# RF.net
KiCad netlist of a schematic drawn in Altium Designer
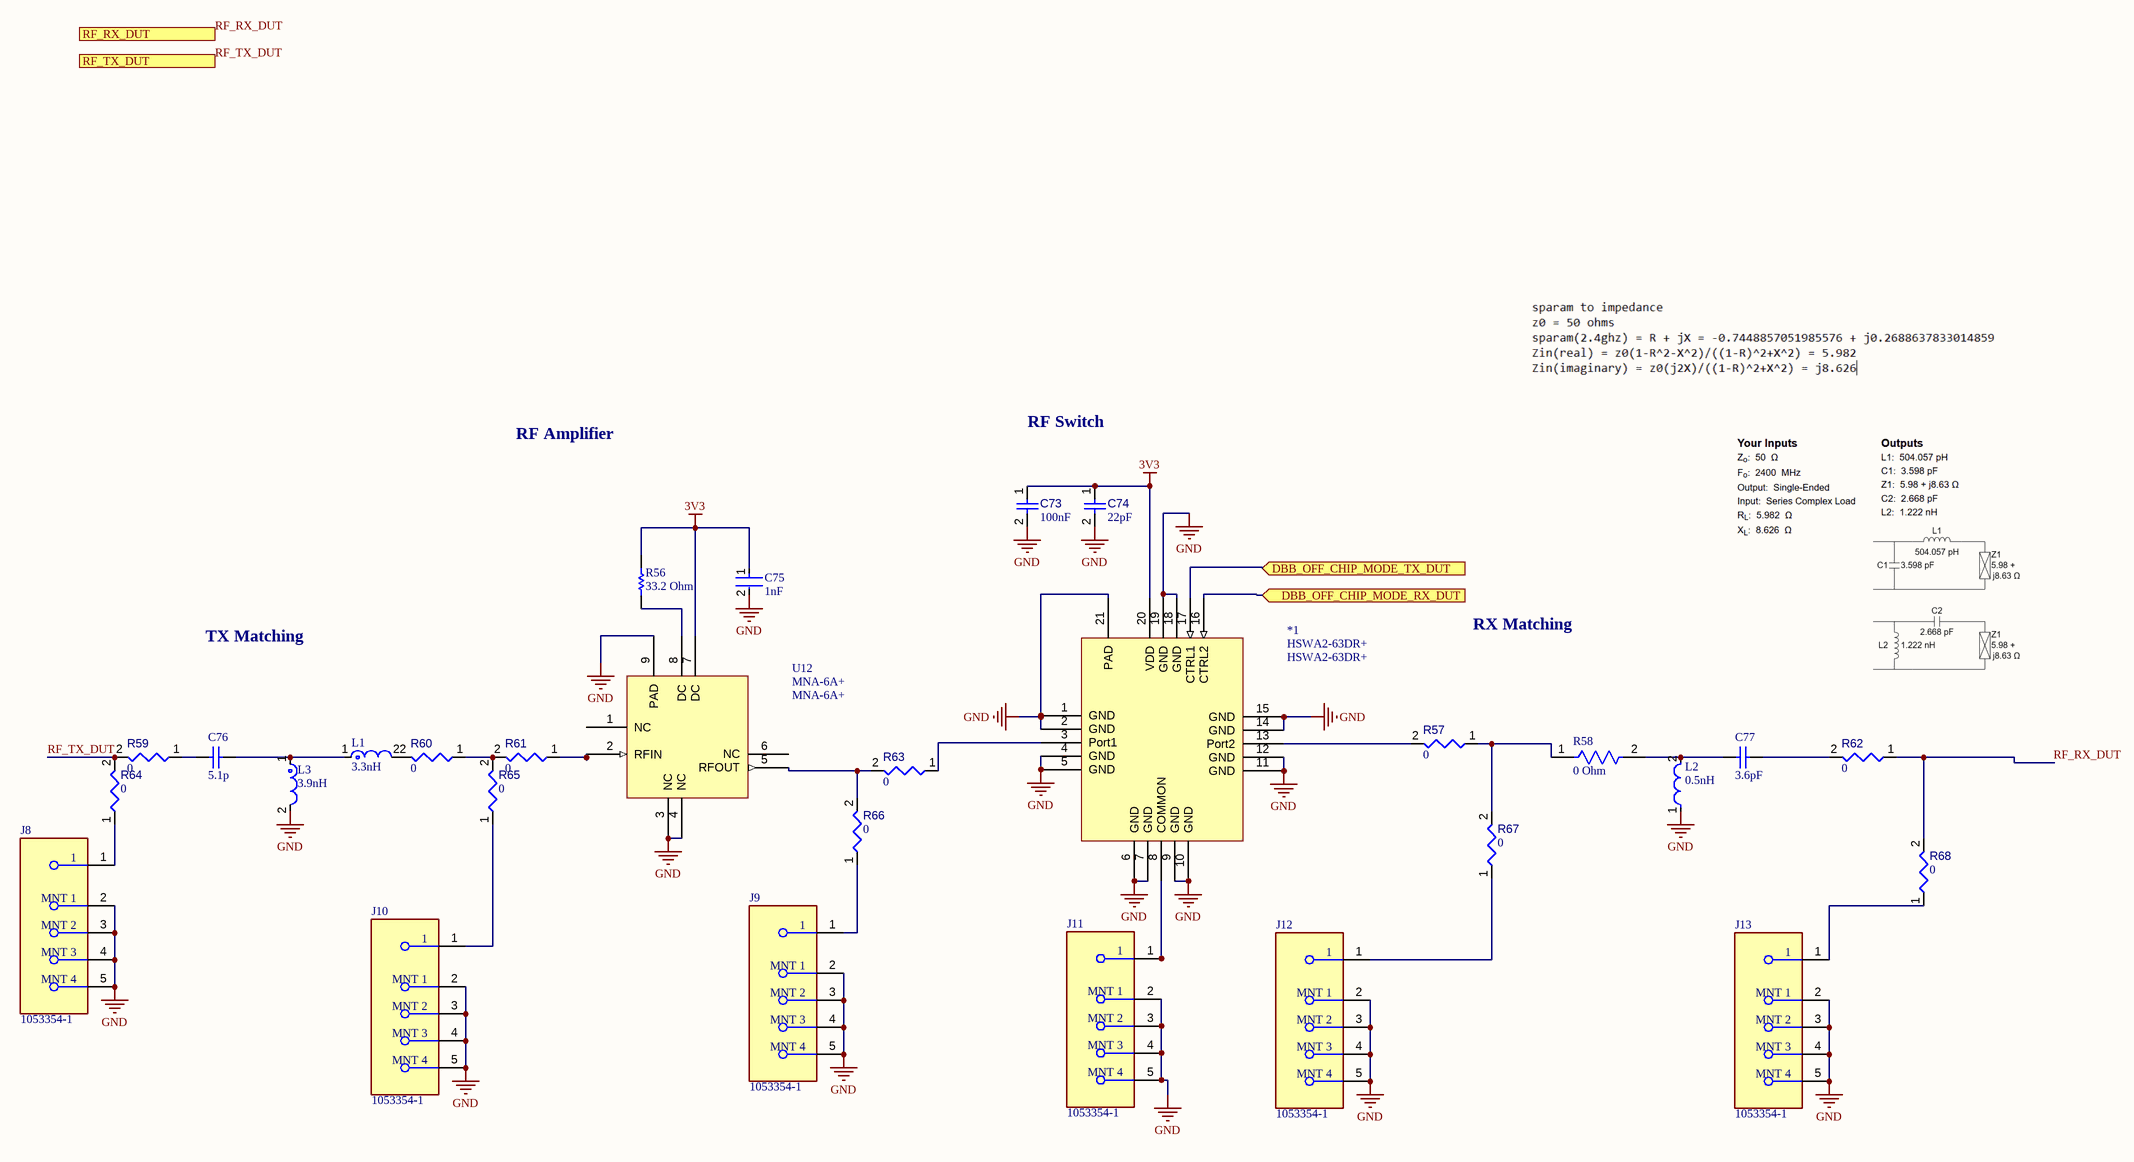
[diagram p0: RF.SchDoc]

(export (version "E")
  (design (tool "Eeschema 10.0.6"))
  (components
    (comp (ref "*1")
      (value "HSWA2-63DR+")
      (footprint "HSWA2-63DR+-Footprint-1")
      (description "Absorptive SPDT, SMT Solid State")
      (fields (field (name "U10") "HSWA2-63DR+") (field (name "MANUFACTURER") "Mini-Circuits"))
      (libsource (lib "EE194 Fall2022") (part "HSWA2-63DR+"))
    )
    (comp (ref "C73")
      (value "100nF")
      (footprint "CAPC1005X56X25LL10T15")
      (description "Chip Capacitor, 0.1 uF, +/- 5%, 16 V, 0402 (1005 Metric)")
      (fields (field (name "TOLERANCE") "5%") (field (name "Comment") "0.1uF"))
      (libsource (lib "EE194 Fall2022") (part "CAP-NP-2"))
    )
    (comp (ref "C74")
      (value "22pF")
      (footprint "CAPC0402(1005)60_L")
      (description "Chip Capacitor, 22pF +/-10%, 50V, 0402, Thickness 0.6 mm")
      (fields (field (name "TOLERANCE") "10%"))
      (libsource (lib "EE194 Fall2022") (part "CAP-NP-2"))
    )
    (comp (ref "C75")
      (value "1nF")
      (footprint "FP-CL10-IPC_C")
      (description "Cap Ceramic 1nF 50V X7R ±10% Pad SMD 0603 +125°C T/R")
      (fields (field (name "VOLTAGE") "50V") (field (name "TOLERANCE") "10%"))
      (libsource (lib "Altium Content Vault") (part "b4654b650e69147ec39a6b967a45e02"))
    )
    (comp (ref "C76")
      (value "5.1p")
      (footprint "CAPC1608X90X35NL15T15")
      (fields
        (field (name "PART NUMBER") "06031A5R1CAT2A")
        (field (name "MANUFACTURER") "AVX Interconnect / Elco")
      )
      (libsource (lib "Altium Content Vault") (part "CAP"))
    )
    (comp (ref "C77")
      (value "3.6pF")
      (footprint "CAPC1608X74X38LL10T13")
      (fields
        (field (name "MANUFACTURER") "AVX Interconnect / Elco")
        (field (name "PART NUMBER") "ML03V13R6BAT2A")
      )
      (libsource (lib "Altium Content Vault") (part "CAP"))
    )
    (comp (ref "J8")
      (value "1053354-1")
      (footprint "FP-1053354-1-MFG")
      (description "CONN SMA JACK STR 50 OHM PCB")
      (libsource (lib "Altium Content Vault") (part "c65b8a639cdaef1819ea20b5466f8fa"))
    )
    (comp (ref "J9")
      (value "1053354-1")
      (footprint "FP-1053354-1-MFG")
      (description "CONN SMA JACK STR 50 OHM PCB")
      (libsource (lib "Altium Content Vault") (part "c65b8a639cdaef1819ea20b5466f8fa"))
    )
    (comp (ref "J10")
      (value "1053354-1")
      (footprint "FP-1053354-1-MFG")
      (description "CONN SMA JACK STR 50 OHM PCB")
      (libsource (lib "Altium Content Vault") (part "c65b8a639cdaef1819ea20b5466f8fa"))
    )
    (comp (ref "J11")
      (value "1053354-1")
      (footprint "FP-1053354-1-MFG")
      (description "CONN SMA JACK STR 50 OHM PCB")
      (libsource (lib "Altium Content Vault") (part "c65b8a639cdaef1819ea20b5466f8fa"))
    )
    (comp (ref "J12")
      (value "1053354-1")
      (footprint "FP-1053354-1-MFG")
      (description "CONN SMA JACK STR 50 OHM PCB")
      (libsource (lib "Altium Content Vault") (part "c65b8a639cdaef1819ea20b5466f8fa"))
    )
    (comp (ref "J13")
      (value "1053354-1")
      (footprint "FP-1053354-1-MFG")
      (description "CONN SMA JACK STR 50 OHM PCB")
      (libsource (lib "Altium Content Vault") (part "c65b8a639cdaef1819ea20b5466f8fa"))
    )
    (comp (ref "L1")
      (value "3.3nH")
      (footprint "FP-LQG18HH_00-MFG")
      (description "Multilayer type RF Inductor 3.3nH ±0.3nH 0.12Ω 1000mA 0603")
      (libsource (lib "Altium Content Vault") (part "4cc4b267dca4c8e51f7102f422741d8"))
    )
    (comp (ref "L2")
      (value "0.5nH")
      (footprint "FP-LQW18AN_00-MFG")
      (description "Wire Wound RF Inductor 5.6nH ±0.5nH 750mA 0.082Ω 0603 (1608)")
      (libsource (lib "Altium Content Vault") (part "725321dda6339637d4d059423bc1c3c"))
    )
    (comp (ref "L3")
      (value "3.9nH")
      (footprint "FP-LQG18HH_00-MFG")
      (description "Multilayer type RF Inductor 3.9nH ±0.3nH 0.15Ω 900mA 0603")
      (libsource (lib "Altium Content Vault") (part "4cc4b267dca4c8e51f7102f422741d8"))
    )
    (comp (ref "R56")
      (value "33.2 Ohm")
      (footprint "RESC1608X55X25NL10T15")
      (fields (field (name "MANUFACTURER") "Yageo") (field (name "PART NUMBER") "RC0603FR-0733R2L"))
      (libsource (lib "Altium Content Vault") (part "RES"))
    )
    (comp (ref "R57")
      (value "0")
      (footprint "RESC0603(1608)_L")
      (description "Jumper 0603 (1608 Metric)")
      (fields (field (name "Comment") "0R3J"))
      (libsource (lib "EE194 Fall2022") (part "0R3J"))
    )
    (comp (ref "R58")
      (value "0 Ohm")
      (footprint "FP-CRCW0603-C-IPC_B")
      (description "RES 0 OHM JUMPER 1/10W 0603")
      (libsource (lib "Altium Content Vault") (part "1029c3af85768c4190bb7ad29bc67b5"))
    )
    (comp (ref "R59")
      (value "0")
      (footprint "RESC0603(1608)_L")
      (description "Jumper 0603 (1608 Metric)")
      (fields (field (name "Comment") "0R3J"))
      (libsource (lib "EE194 Fall2022") (part "0R3J"))
    )
    (comp (ref "R60")
      (value "0")
      (footprint "RESC0603(1608)_L")
      (description "Jumper 0603 (1608 Metric)")
      (fields (field (name "Comment") "0R3J"))
      (libsource (lib "EE194 Fall2022") (part "0R3J"))
    )
    (comp (ref "R61")
      (value "0")
      (footprint "RESC0603(1608)_L")
      (description "Jumper 0603 (1608 Metric)")
      (fields (field (name "Comment") "0R3J"))
      (libsource (lib "EE194 Fall2022") (part "0R3J"))
    )
    (comp (ref "R62")
      (value "0")
      (footprint "RESC0603(1608)_L")
      (description "Jumper 0603 (1608 Metric)")
      (fields (field (name "Comment") "0R3J"))
      (libsource (lib "EE194 Fall2022") (part "0R3J"))
    )
    (comp (ref "R63")
      (value "0")
      (footprint "RESC0603(1608)_L")
      (description "Jumper 0603 (1608 Metric)")
      (fields (field (name "Comment") "0R3J"))
      (libsource (lib "EE194 Fall2022") (part "0R3J"))
    )
    (comp (ref "R64")
      (value "0")
      (footprint "RESC0603(1608)_L")
      (description "Jumper 0603 (1608 Metric)")
      (fields (field (name "Comment") "0R3J"))
      (libsource (lib "EE194 Fall2022") (part "0R3J"))
    )
    (comp (ref "R65")
      (value "0")
      (footprint "RESC0603(1608)_L")
      (description "Jumper 0603 (1608 Metric)")
      (fields (field (name "Comment") "0R3J"))
      (libsource (lib "EE194 Fall2022") (part "0R3J"))
    )
    (comp (ref "R66")
      (value "0")
      (footprint "RESC0603(1608)_L")
      (description "Jumper 0603 (1608 Metric)")
      (fields (field (name "Comment") "0R3J"))
      (libsource (lib "EE194 Fall2022") (part "0R3J"))
    )
    (comp (ref "R67")
      (value "0")
      (footprint "RESC0603(1608)_L")
      (description "Jumper 0603 (1608 Metric)")
      (fields (field (name "Comment") "0R3J"))
      (libsource (lib "EE194 Fall2022") (part "0R3J"))
    )
    (comp (ref "R68")
      (value "0")
      (footprint "RESC0603(1608)_L")
      (description "Jumper 0603 (1608 Metric)")
      (fields (field (name "Comment") "0R3J"))
      (libsource (lib "EE194 Fall2022") (part "0R3J"))
    )
    (comp (ref "U12")
      (value "MNA-6A+")
      (footprint "MNA-6A+-Footprint-1")
      (description "RF Amp Single MMIC Amp 2.5GHz 5V 8-Pin Case DQ-849 T/R")
      (fields (field (name "U11") "MNA-6A+") (field (name "MANUFACTURER") "Mini-Circuits"))
      (libsource (lib "EE194 Fall2022") (part "MNA-6A+"))
    )
  )
  (nets
    (net (code "1") (name "/DBB_OFF_CHIP_MODE_RX_DUT") (class "Default")
      (node (ref "*1") (pin "16") (pinfunction "CTRL2_16") (pintype "input"))
    )
    (net (code "2") (name "/DBB_OFF_CHIP_MODE_TX_DUT") (class "Default")
      (node (ref "*1") (pin "17") (pinfunction "CTRL1_17") (pintype "input"))
    )
    (net (code "3") (name "/RF_RX_DUT") (class "Default")
      (node (ref "R62") (pin "1") (pinfunction "1_1") (pintype "passive"))
      (node (ref "R68") (pin "2") (pinfunction "2_2") (pintype "passive"))
    )
    (net (code "4") (name "/RF_TX_DUT") (class "Default")
      (node (ref "R59") (pin "2") (pinfunction "2_2") (pintype "passive"))
      (node (ref "R64") (pin "2") (pinfunction "2_2") (pintype "passive"))
    )
    (net (code "5") (name "3V3") (class "Default")
      (node (ref "*1") (pin "20") (pinfunction "VDD_20") (pintype "passive"))
      (node (ref "C73") (pin "1") (pinfunction "1_1") (pintype "passive"))
      (node (ref "C74") (pin "1") (pinfunction "1_1") (pintype "passive"))
      (node (ref "C75") (pin "1") (pinfunction "1_1") (pintype "passive"))
      (node (ref "R56") (pin "2") (pinfunction "2_2") (pintype "passive"))
      (node (ref "U12") (pin "7") (pinfunction "DC_7") (pintype "passive"))
    )
    (net (code "6") (name "GND") (class "Default")
      (node (ref "*1") (pin "1") (pinfunction "GND_1") (pintype "passive"))
      (node (ref "*1") (pin "10") (pinfunction "GND_10") (pintype "passive"))
      (node (ref "*1") (pin "11") (pinfunction "GND_11") (pintype "passive"))
      (node (ref "*1") (pin "12") (pinfunction "GND_12") (pintype "passive"))
      (node (ref "*1") (pin "14") (pinfunction "GND_14") (pintype "passive"))
      (node (ref "*1") (pin "15") (pinfunction "GND_15") (pintype "passive"))
      (node (ref "*1") (pin "18") (pinfunction "GND_18") (pintype "passive"))
      (node (ref "*1") (pin "19") (pinfunction "GND_19") (pintype "passive"))
      (node (ref "*1") (pin "2") (pinfunction "GND_2") (pintype "passive"))
      (node (ref "*1") (pin "21") (pinfunction "PAD_21") (pintype "passive"))
      (node (ref "*1") (pin "4") (pinfunction "GND_4") (pintype "passive"))
      (node (ref "*1") (pin "5") (pinfunction "GND_5") (pintype "passive"))
      (node (ref "*1") (pin "6") (pinfunction "GND_6") (pintype "passive"))
      (node (ref "*1") (pin "7") (pinfunction "GND_7") (pintype "passive"))
      (node (ref "*1") (pin "9") (pinfunction "GND_9") (pintype "passive"))
      (node (ref "C73") (pin "2") (pinfunction "2_2") (pintype "passive"))
      (node (ref "C74") (pin "2") (pinfunction "2_2") (pintype "passive"))
      (node (ref "C75") (pin "2") (pinfunction "2_2") (pintype "passive"))
      (node (ref "J10") (pin "2") (pinfunction "MNT_1_2") (pintype "passive"))
      (node (ref "J10") (pin "3") (pinfunction "MNT_2_3") (pintype "passive"))
      (node (ref "J10") (pin "4") (pinfunction "MNT_3_4") (pintype "passive"))
      (node (ref "J10") (pin "5") (pinfunction "MNT_4_5") (pintype "passive"))
      (node (ref "J11") (pin "2") (pinfunction "MNT_1_2") (pintype "passive"))
      (node (ref "J11") (pin "3") (pinfunction "MNT_2_3") (pintype "passive"))
      (node (ref "J11") (pin "4") (pinfunction "MNT_3_4") (pintype "passive"))
      (node (ref "J11") (pin "5") (pinfunction "MNT_4_5") (pintype "passive"))
      (node (ref "J12") (pin "2") (pinfunction "MNT_1_2") (pintype "passive"))
      (node (ref "J12") (pin "3") (pinfunction "MNT_2_3") (pintype "passive"))
      (node (ref "J12") (pin "4") (pinfunction "MNT_3_4") (pintype "passive"))
      (node (ref "J12") (pin "5") (pinfunction "MNT_4_5") (pintype "passive"))
      (node (ref "J13") (pin "2") (pinfunction "MNT_1_2") (pintype "passive"))
      (node (ref "J13") (pin "3") (pinfunction "MNT_2_3") (pintype "passive"))
      (node (ref "J13") (pin "4") (pinfunction "MNT_3_4") (pintype "passive"))
      (node (ref "J13") (pin "5") (pinfunction "MNT_4_5") (pintype "passive"))
      (node (ref "J8") (pin "2") (pinfunction "MNT_1_2") (pintype "passive"))
      (node (ref "J8") (pin "3") (pinfunction "MNT_2_3") (pintype "passive"))
      (node (ref "J8") (pin "4") (pinfunction "MNT_3_4") (pintype "passive"))
      (node (ref "J8") (pin "5") (pinfunction "MNT_4_5") (pintype "passive"))
      (node (ref "J9") (pin "2") (pinfunction "MNT_1_2") (pintype "passive"))
      (node (ref "J9") (pin "3") (pinfunction "MNT_2_3") (pintype "passive"))
      (node (ref "J9") (pin "4") (pinfunction "MNT_3_4") (pintype "passive"))
      (node (ref "J9") (pin "5") (pinfunction "MNT_4_5") (pintype "passive"))
      (node (ref "L2") (pin "1") (pinfunction "1_1") (pintype "passive"))
      (node (ref "L3") (pin "2") (pinfunction "2_2") (pintype "passive"))
      (node (ref "U12") (pin "3") (pinfunction "NC_3") (pintype "passive"))
      (node (ref "U12") (pin "4") (pinfunction "NC_4") (pintype "passive"))
      (node (ref "U12") (pin "9") (pinfunction "PAD_9") (pintype "passive"))
    )
    (net (code "7") (name "Net-(*1-COMMON)") (class "Default")
      (node (ref "*1") (pin "8") (pinfunction "COMMON_8") (pintype "passive"))
      (node (ref "J11") (pin "1") (pinfunction "1_1") (pintype "passive"))
    )
    (net (code "8") (name "Net-(*1-Port1)") (class "Default")
      (node (ref "*1") (pin "3") (pinfunction "Port1_3") (pintype "passive"))
      (node (ref "R63") (pin "1") (pinfunction "1_1") (pintype "passive"))
    )
    (net (code "9") (name "Net-(*1-Port2)") (class "Default")
      (node (ref "*1") (pin "13") (pinfunction "Port2_13") (pintype "passive"))
      (node (ref "R57") (pin "2") (pinfunction "2_2") (pintype "passive"))
    )
    (net (code "10") (name "Net-(C76-Pad1)") (class "Default")
      (node (ref "C76") (pin "1") (pinfunction "1_1") (pintype "passive"))
      (node (ref "R59") (pin "1") (pinfunction "1_1") (pintype "passive"))
    )
    (net (code "11") (name "Net-(C76-Pad2)") (class "Default")
      (node (ref "C76") (pin "2") (pinfunction "2_2") (pintype "passive"))
      (node (ref "L1") (pin "1") (pinfunction "1_1") (pintype "passive"))
      (node (ref "L3") (pin "1") (pinfunction "1_1") (pintype "passive"))
    )
    (net (code "12") (name "Net-(C77-Pad1)") (class "Default")
      (node (ref "C77") (pin "1") (pinfunction "1_1") (pintype "passive"))
      (node (ref "L2") (pin "2") (pinfunction "2_2") (pintype "passive"))
      (node (ref "R58") (pin "2") (pinfunction "2_2") (pintype "passive"))
    )
    (net (code "13") (name "Net-(C77-Pad2)") (class "Default")
      (node (ref "C77") (pin "2") (pinfunction "2_2") (pintype "passive"))
      (node (ref "R62") (pin "2") (pinfunction "2_2") (pintype "passive"))
    )
    (net (code "14") (name "Net-(J8-Pad1)") (class "Default")
      (node (ref "J8") (pin "1") (pinfunction "1_1") (pintype "passive"))
      (node (ref "R64") (pin "1") (pinfunction "1_1") (pintype "passive"))
    )
    (net (code "15") (name "Net-(J9-Pad1)") (class "Default")
      (node (ref "J9") (pin "1") (pinfunction "1_1") (pintype "passive"))
      (node (ref "R66") (pin "1") (pinfunction "1_1") (pintype "passive"))
    )
    (net (code "16") (name "Net-(J10-Pad1)") (class "Default")
      (node (ref "J10") (pin "1") (pinfunction "1_1") (pintype "passive"))
      (node (ref "R65") (pin "1") (pinfunction "1_1") (pintype "passive"))
    )
    (net (code "17") (name "Net-(J12-Pad1)") (class "Default")
      (node (ref "J12") (pin "1") (pinfunction "1_1") (pintype "passive"))
      (node (ref "R67") (pin "1") (pinfunction "1_1") (pintype "passive"))
    )
    (net (code "18") (name "Net-(J13-Pad1)") (class "Default")
      (node (ref "J13") (pin "1") (pinfunction "1_1") (pintype "passive"))
      (node (ref "R68") (pin "1") (pinfunction "1_1") (pintype "passive"))
    )
    (net (code "19") (name "Net-(L1-Pad2)") (class "Default")
      (node (ref "L1") (pin "2") (pinfunction "2_2") (pintype "passive"))
      (node (ref "R60") (pin "2") (pinfunction "2_2") (pintype "passive"))
    )
    (net (code "20") (name "Net-(R56-Pad1)") (class "Default")
      (node (ref "R56") (pin "1") (pinfunction "1_1") (pintype "passive"))
      (node (ref "U12") (pin "8") (pinfunction "DC_8") (pintype "passive"))
    )
    (net (code "21") (name "Net-(R57-Pad1)") (class "Default")
      (node (ref "R57") (pin "1") (pinfunction "1_1") (pintype "passive"))
      (node (ref "R58") (pin "1") (pinfunction "1_1") (pintype "passive"))
      (node (ref "R67") (pin "2") (pinfunction "2_2") (pintype "passive"))
    )
    (net (code "22") (name "Net-(R60-Pad1)") (class "Default")
      (node (ref "R60") (pin "1") (pinfunction "1_1") (pintype "passive"))
      (node (ref "R61") (pin "2") (pinfunction "2_2") (pintype "passive"))
      (node (ref "R65") (pin "2") (pinfunction "2_2") (pintype "passive"))
    )
    (net (code "23") (name "Net-(U12-RFIN)") (class "Default")
      (node (ref "R61") (pin "1") (pinfunction "1_1") (pintype "passive"))
      (node (ref "U12") (pin "2") (pinfunction "RFIN_2") (pintype "input"))
    )
    (net (code "24") (name "Net-(U12-RFOUT)") (class "Default")
      (node (ref "R63") (pin "2") (pinfunction "2_2") (pintype "passive"))
      (node (ref "R66") (pin "2") (pinfunction "2_2") (pintype "passive"))
      (node (ref "U12") (pin "5") (pinfunction "RFOUT_5") (pintype "output"))
    )
    (net (code "25") (name "unconnected-(U12-NC-Pad1)") (class "Default")
      (node (ref "U12") (pin "1") (pinfunction "NC_1") (pintype "passive"))
    )
    (net (code "26") (name "unconnected-(U12-NC-Pad6)") (class "Default")
      (node (ref "U12") (pin "6") (pinfunction "NC_6") (pintype "passive"))
    )
  )
)
